# Connectors.net
KiCad netlist of a schematic drawn in Altium Designer
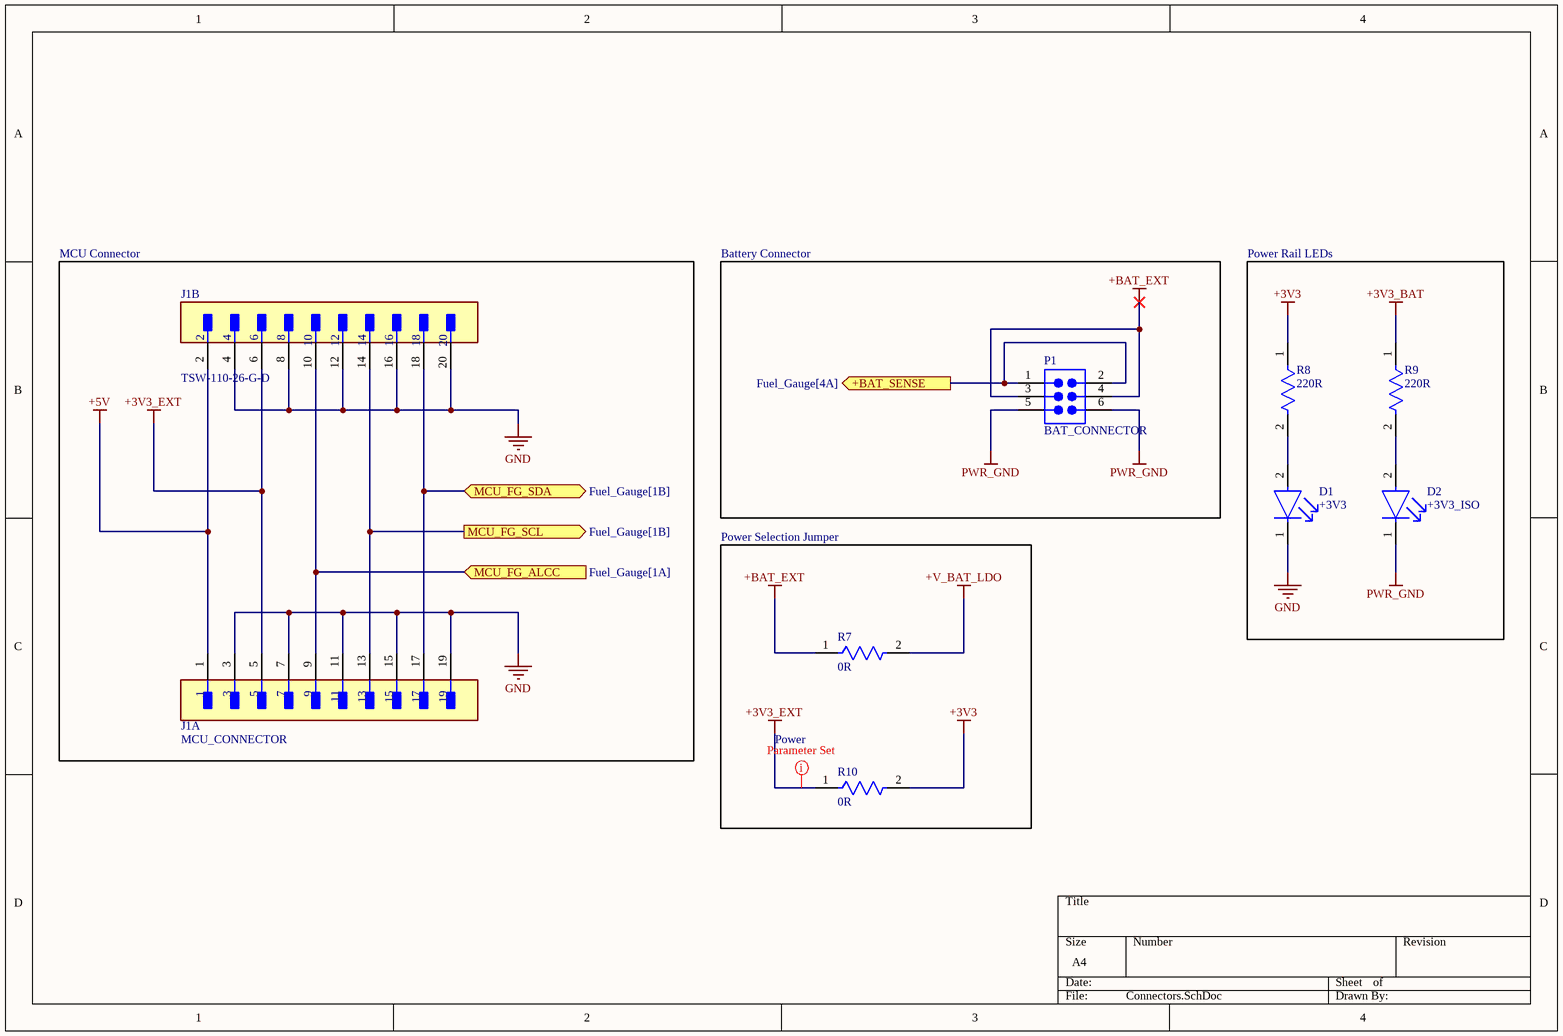
[diagram p0: Connectors.SchDoc]

(export (version "E")
  (design (tool "Eeschema 10.0.6"))
  (components
    (comp (ref "D1")
      (value "+3V3")
      (footprint "FP-LTST-C170GKT-MFG")
      (description "LED GREEN CLEAR SMD")
      (fields (field (name "VOLTAGE") "5V"))
      (libsource (lib "Altium Content Vault") (part "8706943c75ba83719d021d2fdc84c58"))
    )
    (comp (ref "D2")
      (value "+3V3_ISO")
      (footprint "FP-LTST-C170GKT-MFG")
      (description "LED GREEN CLEAR SMD")
      (fields (field (name "VOLTAGE") "5V"))
      (libsource (lib "Altium Content Vault") (part "8706943c75ba83719d021d2fdc84c58"))
    )
    (comp (ref "J1")
      (value "MCU_CONNECTOR")
      (footprint "FP-TSW-110-26-G-D-MFG")
      (description "CONN HEADER VERT 20POS 2.54MM")
      (fields
        (field (name "OCTOPART") "https://octopart.com/tsw-110-26-g-d-samtec-274552")
        (field (name "MANUFACTURER") "Samtec")
        (field (name "MANUFACTURER PART NUMBER") "TSW-110-26-G-D")
      )
      (libsource (lib "Altium Content Vault") (part "3c9050f31bf3a235369f849c918cfe7"))
    )
    (comp (ref "P1")
      (value "BAT_CONNECTOR")
      (footprint "SMTC-TSW-103-08-X-D")
      (description "0.025\" SQ Post Header, Through-hole, Vertical, -55 to 125 degC, 2.54 mm Pitch, 6-Pin, Male, RoHS")
      (fields (field (name "MANUFACTURER") "Samtec") (field (name "PARTNUMBER") "TSW-103-08-G-D"))
      (libsource (lib "Altium Content Vault") (part "SMTC-TSW-103-08-X-D"))
    )
    (comp (ref "R7")
      (value "0R")
      (footprint "FP-AF0805-IPC_B")
      (description "Anti-Sulfurated Chip Resistor Automotive Grade 0Ω Jumper 0.125W 0805")
      (libsource (lib "Altium Content Vault") (part "1029c3af85768c4190bb7ad29bc67b5"))
    )
    (comp (ref "R8")
      (value "220R")
      (footprint "FP-RT0805-MFG")
      (description "RES SMD 220 OHM 1% 1/8W 0805")
      (fields
        (field (name "OCTOPART") "https://octopart.com/rt0805fre07220rl-yageo-39797223")
        (field (name "MANUFACTURER PART NUMBER") "RT0805FRE07220RL")
      )
      (libsource (lib "Altium Content Vault") (part "1029c3af85768c4190bb7ad29bc67b5"))
    )
    (comp (ref "R9")
      (value "220R")
      (footprint "FP-RT0805-MFG")
      (description "RES SMD 220 OHM 1% 1/8W 0805")
      (fields
        (field (name "OCTOPART") "https://octopart.com/rt0805fre07220rl-yageo-39797223")
        (field (name "MANUFACTURER PART NUMBER") "RT0805FRE07220RL")
      )
      (libsource (lib "Altium Content Vault") (part "1029c3af85768c4190bb7ad29bc67b5"))
    )
    (comp (ref "R10")
      (value "0R")
      (footprint "FP-AF0805-IPC_B")
      (description "Anti-Sulfurated Chip Resistor Automotive Grade 0Ω Jumper 0.125W 0805")
      (libsource (lib "Altium Content Vault") (part "1029c3af85768c4190bb7ad29bc67b5"))
    )
  )
  (nets
    (net (code "1") (name "+3V3") (class "Default")
      (node (ref "R10") (pin "2") (pinfunction "2_2") (pintype "passive"))
      (node (ref "R8") (pin "1") (pinfunction "1_1") (pintype "passive"))
    )
    (net (code "2") (name "+3V3_BAT") (class "Default")
      (node (ref "R9") (pin "1") (pinfunction "1_1") (pintype "passive"))
    )
    (net (code "3") (name "+3V3_EXT") (class "Default")
      (node (ref "J1") (pin "5") (pinfunction "5_5") (pintype "passive"))
      (node (ref "J1") (pin "6") (pinfunction "6_6") (pintype "passive"))
      (node (ref "R10") (pin "1") (pinfunction "1_1") (pintype "passive"))
    )
    (net (code "4") (name "+5V") (class "Default")
      (node (ref "J1") (pin "1") (pinfunction "1_1") (pintype "passive"))
      (node (ref "J1") (pin "2") (pinfunction "2_2") (pintype "passive"))
    )
    (net (code "5") (name "+BAT_EXT") (class "Default")
      (node (ref "P1") (pin "3") (pinfunction "3_3") (pintype "passive"))
      (node (ref "P1") (pin "4") (pinfunction "4_4") (pintype "passive"))
      (node (ref "R7") (pin "1") (pinfunction "1_1") (pintype "passive"))
    )
    (net (code "6") (name "+V_BAT_LDO") (class "Default")
      (node (ref "R7") (pin "2") (pinfunction "2_2") (pintype "passive"))
    )
    (net (code "7") (name "/+BAT_SENSE") (class "Default")
      (node (ref "P1") (pin "1") (pinfunction "1_1") (pintype "passive"))
      (node (ref "P1") (pin "2") (pinfunction "2_2") (pintype "passive"))
    )
    (net (code "8") (name "/MCU_FG_ALCC") (class "Default")
      (node (ref "J1") (pin "10") (pinfunction "10_10") (pintype "passive"))
      (node (ref "J1") (pin "9") (pinfunction "9_9") (pintype "passive"))
    )
    (net (code "9") (name "/MCU_FG_SCL") (class "Default")
      (node (ref "J1") (pin "13") (pinfunction "13_13") (pintype "passive"))
      (node (ref "J1") (pin "14") (pinfunction "14_14") (pintype "passive"))
    )
    (net (code "10") (name "/MCU_FG_SDA") (class "Default")
      (node (ref "J1") (pin "17") (pinfunction "17_17") (pintype "passive"))
      (node (ref "J1") (pin "18") (pinfunction "18_18") (pintype "passive"))
    )
    (net (code "11") (name "GND") (class "Default")
      (node (ref "D1") (pin "1") (pinfunction "C_1") (pintype "passive"))
      (node (ref "J1") (pin "11") (pinfunction "11_11") (pintype "passive"))
      (node (ref "J1") (pin "12") (pinfunction "12_12") (pintype "passive"))
      (node (ref "J1") (pin "15") (pinfunction "15_15") (pintype "passive"))
      (node (ref "J1") (pin "16") (pinfunction "16_16") (pintype "passive"))
      (node (ref "J1") (pin "19") (pinfunction "19_19") (pintype "passive"))
      (node (ref "J1") (pin "20") (pinfunction "20_20") (pintype "passive"))
      (node (ref "J1") (pin "3") (pinfunction "3_3") (pintype "passive"))
      (node (ref "J1") (pin "4") (pinfunction "4_4") (pintype "passive"))
      (node (ref "J1") (pin "7") (pinfunction "7_7") (pintype "passive"))
      (node (ref "J1") (pin "8") (pinfunction "8_8") (pintype "passive"))
    )
    (net (code "12") (name "Net-(D1-A)") (class "Default")
      (node (ref "D1") (pin "2") (pinfunction "A_2") (pintype "passive"))
      (node (ref "R8") (pin "2") (pinfunction "2_2") (pintype "passive"))
    )
    (net (code "13") (name "Net-(D2-A)") (class "Default")
      (node (ref "D2") (pin "2") (pinfunction "A_2") (pintype "passive"))
      (node (ref "R9") (pin "2") (pinfunction "2_2") (pintype "passive"))
    )
    (net (code "14") (name "PWR_GND") (class "Default")
      (node (ref "D2") (pin "1") (pinfunction "C_1") (pintype "passive"))
      (node (ref "P1") (pin "5") (pinfunction "5_5") (pintype "passive"))
      (node (ref "P1") (pin "6") (pinfunction "6_6") (pintype "passive"))
    )
  )
)
